# attiny84.net
KiCad netlist of a schematic drawn in EAGLE
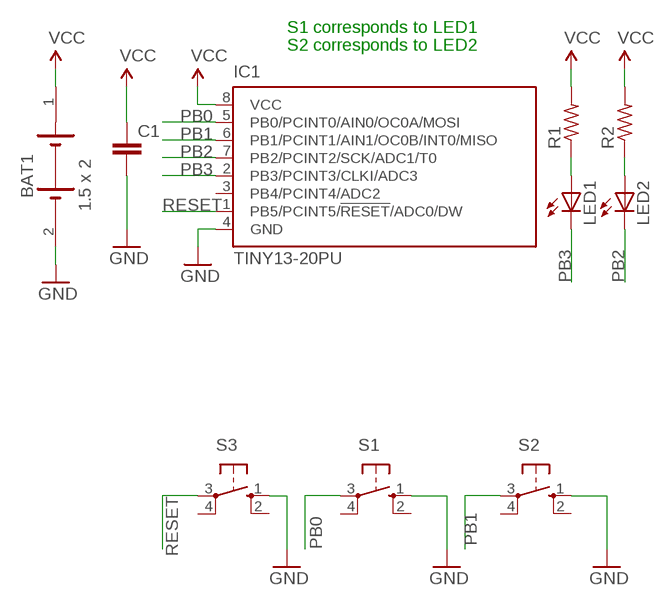
[diagram p0: schematic, sheet 1]

(export (version "E")
  (design (tool "Eeschema 10.0.6"))
  (components
    (comp (ref "BAT1")
      (value "1.5 x 2")
      (footprint "eagle-import:RELIMATE")
      (libsource (lib "eagle-import") (part "1.5X2BATTERYRELIMATE"))
    )
    (comp (ref "C1")
      (value "C2.5/2")
      (footprint "eagle-import:C2.5-2")
      (libsource (lib "eagle-import") (part "C2.5/2"))
    )
    (comp (ref "IC1")
      (value "TINY13-20PU")
      (footprint "eagle-import:DIL08")
      (libsource (lib "eagle-import") (part "TINY13PU-20"))
    )
    (comp (ref "LED1")
      (value "LED3MM")
      (footprint "eagle-import:LED3MM")
      (libsource (lib "eagle-import") (part "LED3MM"))
    )
    (comp (ref "LED2")
      (value "LED3MM")
      (footprint "eagle-import:LED3MM")
      (libsource (lib "eagle-import") (part "LED3MM"))
    )
    (comp (ref "R1")
      (value "R-US_0207/10")
      (footprint "eagle-import:0207_10")
      (libsource (lib "eagle-import") (part "R-US_0207/10"))
    )
    (comp (ref "R2")
      (value "R-US_0207/10")
      (footprint "eagle-import:0207_10")
      (libsource (lib "eagle-import") (part "R-US_0207/10"))
    )
    (comp (ref "S1")
      (value "10-XX")
      (footprint "eagle-import:B3F-10XX")
      (libsource (lib "eagle-import") (part "10-XX"))
    )
    (comp (ref "S2")
      (value "10-XX")
      (footprint "eagle-import:B3F-10XX")
      (libsource (lib "eagle-import") (part "10-XX"))
    )
    (comp (ref "S3")
      (value "10-XX")
      (footprint "eagle-import:B3F-10XX")
      (libsource (lib "eagle-import") (part "10-XX"))
    )
  )
  (nets
    (net (code "1") (name "/PB0") (class "Default")
      (node (ref "IC1") (pin "5") (pinfunction "PB0/PCINT0/AIN0/OC0A/MOSI_5") (pintype "bidirectional"))
      (node (ref "S1") (pin "3") (pinfunction "P_3") (pintype "passive"))
    )
    (net (code "2") (name "/PB1") (class "Default")
      (node (ref "IC1") (pin "6") (pinfunction "PB1/PCINT1/AIN1/OC0B/INT0/MISO_6") (pintype "bidirectional"))
      (node (ref "S2") (pin "3") (pinfunction "P_3") (pintype "passive"))
    )
    (net (code "3") (name "/PB2") (class "Default")
      (node (ref "IC1") (pin "7") (pinfunction "PB2/PCINT2/SCK/ADC1/T0_7") (pintype "bidirectional"))
      (node (ref "LED2") (pin "K") (pinfunction "C_K") (pintype "passive"))
    )
    (net (code "4") (name "/PB3") (class "Default")
      (node (ref "IC1") (pin "2") (pinfunction "PB3/PCINT3/CLKI/ADC3_2") (pintype "bidirectional"))
      (node (ref "LED1") (pin "K") (pinfunction "C_K") (pintype "passive"))
    )
    (net (code "5") (name "/RESET") (class "Default")
      (node (ref "IC1") (pin "1") (pinfunction "PB5/PCINT5/~{RESET}/ADC0/DW_1") (pintype "bidirectional"))
      (node (ref "S3") (pin "3") (pinfunction "P_3") (pintype "passive"))
    )
    (net (code "6") (name "GND") (class "Default")
      (node (ref "BAT1") (pin "2") (pinfunction "2_2") (pintype "power_in"))
      (node (ref "C1") (pin "2") (pinfunction "2_2") (pintype "passive"))
      (node (ref "IC1") (pin "4") (pinfunction "GND_4") (pintype "power_in"))
      (node (ref "S1") (pin "1") (pinfunction "S_1") (pintype "passive"))
      (node (ref "S2") (pin "1") (pinfunction "S_1") (pintype "passive"))
      (node (ref "S3") (pin "1") (pinfunction "S_1") (pintype "passive"))
    )
    (net (code "7") (name "Net-(LED1-PadA)") (class "Default")
      (node (ref "LED1") (pin "A") (pinfunction "A_A") (pintype "passive"))
      (node (ref "R1") (pin "1") (pinfunction "1_1") (pintype "passive"))
    )
    (net (code "8") (name "Net-(LED2-PadA)") (class "Default")
      (node (ref "LED2") (pin "A") (pinfunction "A_A") (pintype "passive"))
      (node (ref "R2") (pin "1") (pinfunction "1_1") (pintype "passive"))
    )
    (net (code "9") (name "VCC") (class "Default")
      (node (ref "BAT1") (pin "1") (pinfunction "1_1") (pintype "power_in"))
      (node (ref "C1") (pin "1") (pinfunction "1_1") (pintype "passive"))
      (node (ref "IC1") (pin "8") (pinfunction "VCC_8") (pintype "power_in"))
      (node (ref "R1") (pin "2") (pinfunction "2_2") (pintype "passive"))
      (node (ref "R2") (pin "2") (pinfunction "2_2") (pintype "passive"))
    )
    (net (code "10") (name "unconnected-(IC1-PB4{slash}PCINT4{slash}ADC2-Pad3)") (class "Default")
      (node (ref "IC1") (pin "3") (pinfunction "PB4/PCINT4/ADC2_3") (pintype "bidirectional"))
    )
    (net (code "11") (name "unconnected-(S1-P1-Pad4)") (class "Default")
      (node (ref "S1") (pin "4") (pinfunction "P1_4") (pintype "passive"))
    )
    (net (code "12") (name "unconnected-(S1-S1-Pad2)") (class "Default")
      (node (ref "S1") (pin "2") (pinfunction "S1_2") (pintype "passive"))
    )
    (net (code "13") (name "unconnected-(S2-P1-Pad4)") (class "Default")
      (node (ref "S2") (pin "4") (pinfunction "P1_4") (pintype "passive"))
    )
    (net (code "14") (name "unconnected-(S2-S1-Pad2)") (class "Default")
      (node (ref "S2") (pin "2") (pinfunction "S1_2") (pintype "passive"))
    )
    (net (code "15") (name "unconnected-(S3-P1-Pad4)") (class "Default")
      (node (ref "S3") (pin "4") (pinfunction "P1_4") (pintype "passive"))
    )
    (net (code "16") (name "unconnected-(S3-S1-Pad2)") (class "Default")
      (node (ref "S3") (pin "2") (pinfunction "S1_2") (pintype "passive"))
    )
  )
)
